# Sheet1.net
KiCad netlist of a schematic drawn in Altium Designer
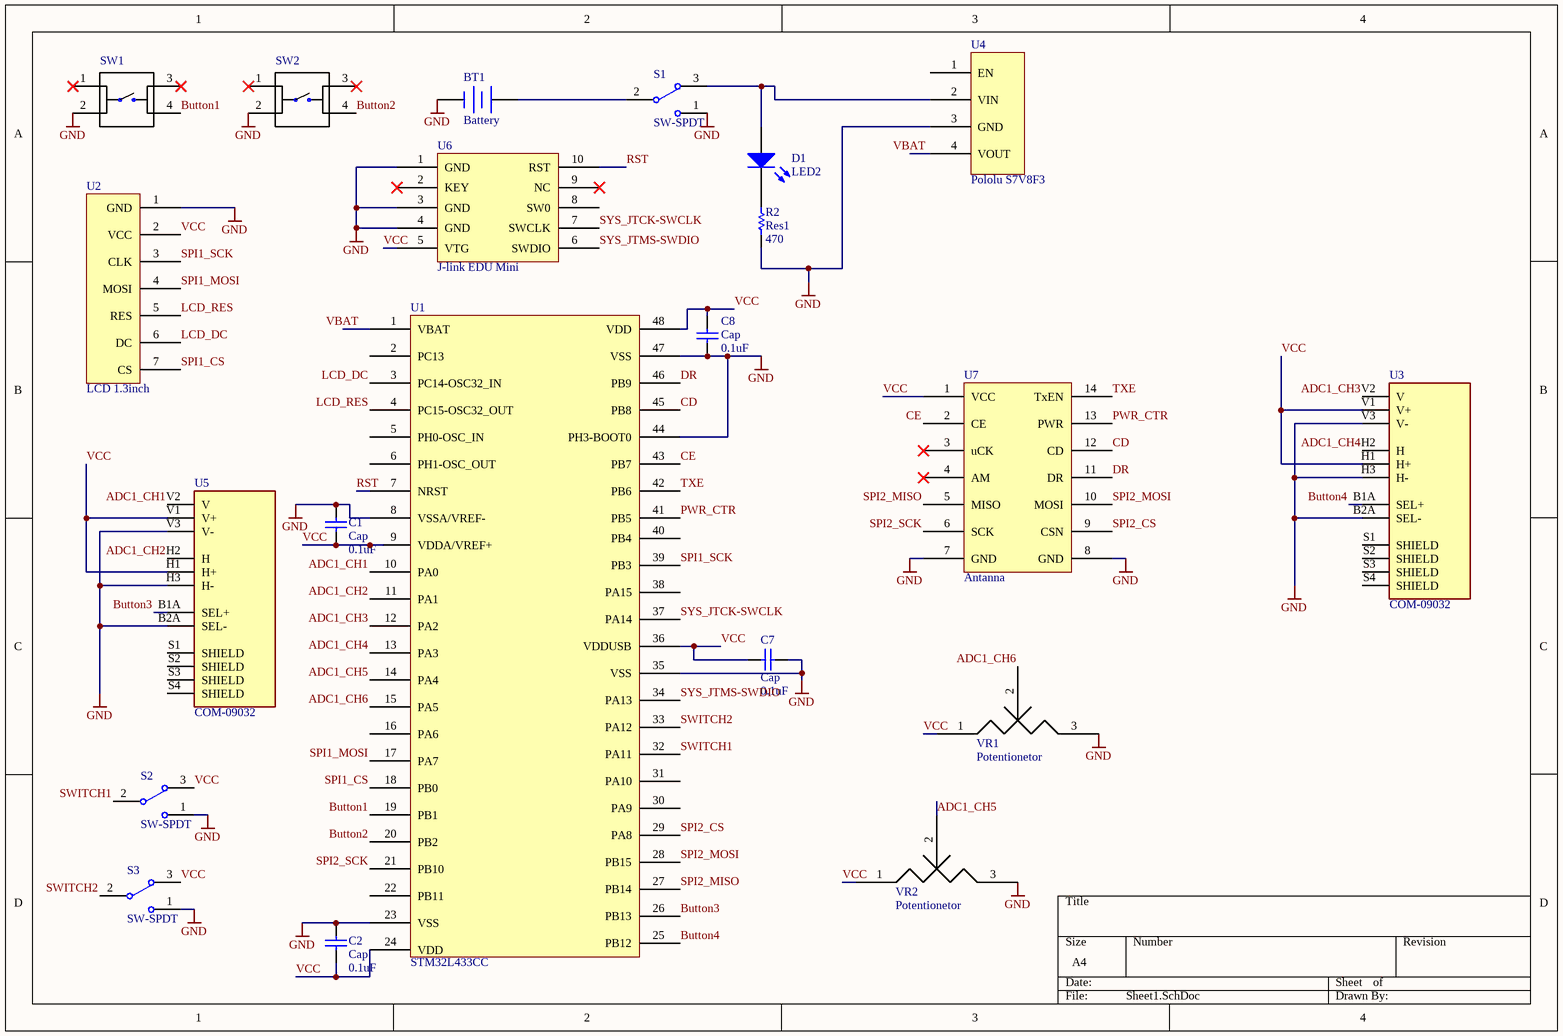
[diagram p0: Sheet1.SchDoc]

(export (version "E")
  (design (tool "Eeschema 10.0.6"))
  (components
    (comp (ref "BT1")
      (value "Battery")
      (footprint "BAT-2")
      (description "Multicell Battery")
      (fields (field (name "PUBLISHER") "Altium Limited"))
      (libsource (lib "Miscellaneous Devices") (part "Battery"))
    )
    (comp (ref "C1")
      (value "Cap")
      (footprint "RESC0603")
      (description "Capacitor")
      (fields (field (name "ALTIUM_VALUE") "0.1uF") (field (name "PUBLISHER") "Altium Limited"))
      (libsource (lib "Miscellaneous Devices") (part "Cap"))
    )
    (comp (ref "C2")
      (value "Cap")
      (footprint "RESC0603")
      (description "Capacitor")
      (fields (field (name "ALTIUM_VALUE") "0.1uF") (field (name "PUBLISHER") "Altium Limited"))
      (libsource (lib "Miscellaneous Devices") (part "Cap"))
    )
    (comp (ref "C7")
      (value "Cap")
      (footprint "RESC0603")
      (description "Capacitor")
      (fields (field (name "ALTIUM_VALUE") "0.1uF") (field (name "PUBLISHER") "Altium Limited"))
      (libsource (lib "Miscellaneous Devices") (part "Cap"))
    )
    (comp (ref "C8")
      (value "Cap")
      (footprint "RESC0603")
      (description "Capacitor")
      (fields (field (name "ALTIUM_VALUE") "0.1uF") (field (name "PUBLISHER") "Altium Limited"))
      (libsource (lib "Miscellaneous Devices") (part "Cap"))
    )
    (comp (ref "D1")
      (value "LED2")
      (footprint "LED1")
      (description "Typical RED, GREEN, YELLOW, AMBER GaAs LED")
      (fields (field (name "PUBLISHER") "Altium Limited"))
      (libsource (lib "Miscellaneous Devices") (part "LED2"))
    )
    (comp (ref "R2")
      (value "Res1")
      (footprint "RESC0603")
      (description "Resistor")
      (fields (field (name "ALTIUM_VALUE") "470") (field (name "PUBLISHER") "Altium Limited"))
      (libsource (lib "Miscellaneous Devices") (part "Res1"))
    )
    (comp (ref "S1")
      (value "SW-SPDT")
      (footprint "Toggle switch")
      (description "SPDT Subminiature Toggle Switch, Right Angle Mounting, Vertical Actuation")
      (fields (field (name "PUBLISHER") "Altium Limited"))
      (libsource (lib "Miscellaneous Devices") (part "SW-SPDT"))
    )
    (comp (ref "S2")
      (value "SW-SPDT")
      (footprint "Toggle switch")
      (description "SPDT Subminiature Toggle Switch, Right Angle Mounting, Vertical Actuation")
      (fields (field (name "PUBLISHER") "Altium Limited"))
      (libsource (lib "Miscellaneous Devices") (part "SW-SPDT"))
    )
    (comp (ref "S3")
      (value "SW-SPDT")
      (footprint "Toggle switch")
      (description "SPDT Subminiature Toggle Switch, Right Angle Mounting, Vertical Actuation")
      (fields (field (name "PUBLISHER") "Altium Limited"))
      (libsource (lib "Miscellaneous Devices") (part "SW-SPDT"))
    )
    (comp (ref "SW1")
      (value "1825910-6")
      (footprint "PUSHBUTTON SWITCH - duplicate")
      (description "6MM TACT SWITCH, HIGH TEMP")
      (fields (field (name "DIGI-KEY_PART_NUMBER") "450-1650-ND") (field (name "MF") "TE Connectivity"))
      (libsource (lib "Schlib1") (part "1825910-6"))
    )
    (comp (ref "SW2")
      (value "1825910-6")
      (footprint "PUSHBUTTON SWITCH - duplicate")
      (description "6MM TACT SWITCH, HIGH TEMP")
      (fields (field (name "DIGI-KEY_PART_NUMBER") "450-1650-ND") (field (name "MF") "TE Connectivity"))
      (libsource (lib "Schlib1") (part "1825910-6"))
    )
    (comp (ref "U1")
      (value "STM32L433CC")
      (footprint "LQFP48")
      (libsource (lib "Schlib1") (part "STM32L433CC"))
    )
    (comp (ref "U2")
      (value "LCD 1.3inch")
      (footprint "LCD")
      (libsource (lib "Schlib_Controller") (part "LCD 1.3inch"))
    )
    (comp (ref "U3")
      (value "COM-09032")
      (footprint "XDCR_COM-09032")
      (description "Joystick, 2 - Axis Analog _Resistive_ Output")
      (fields (field (name "MF") "SparkFun Electronics"))
      (libsource (lib "Schlib_Controller") (part "COM-09032"))
    )
    (comp (ref "U4")
      (value "Pololu S7V8F3")
      (footprint "Pololu S7V8F3")
      (libsource (lib "Schlib1") (part "Pololu S7V8F3"))
    )
    (comp (ref "U5")
      (value "COM-09032")
      (footprint "XDCR_COM-09032")
      (description "Joystick, 2 - Axis Analog _Resistive_ Output")
      (fields (field (name "MF") "SparkFun Electronics"))
      (libsource (lib "Schlib_Controller") (part "COM-09032"))
    )
    (comp (ref "U6")
      (value "J-link EDU Mini")
      (footprint "10 pin vertical")
      (libsource (lib "Schlib1") (part "J-link EDU Mini"))
    )
    (comp (ref "U7")
      (value "Antanna")
      (footprint "Antanna")
      (libsource (lib "Schlib_Controller") (part "Antanna"))
    )
    (comp (ref "VR1")
      (value "Potentionetor")
      (footprint "potentiometer")
      (libsource (lib "Schlib_Controller") (part "Potentionetor"))
    )
    (comp (ref "VR2")
      (value "Potentionetor")
      (footprint "potentiometer")
      (libsource (lib "Schlib_Controller") (part "Potentionetor"))
    )
  )
  (nets
    (net (code "1") (name "/ADC1_CH1") (class "Default")
      (node (ref "U1") (pin "10") (pinfunction "PA0_10") (pintype "passive"))
      (node (ref "U5") (pin "V2") (pinfunction "V_V2") (pintype "passive"))
    )
    (net (code "2") (name "/ADC1_CH2") (class "Default")
      (node (ref "U1") (pin "11") (pinfunction "PA1_11") (pintype "passive"))
      (node (ref "U5") (pin "H2") (pinfunction "H_H2") (pintype "passive"))
    )
    (net (code "3") (name "/ADC1_CH3") (class "Default")
      (node (ref "U1") (pin "12") (pinfunction "PA2_12") (pintype "passive"))
      (node (ref "U3") (pin "V2") (pinfunction "V_V2") (pintype "passive"))
    )
    (net (code "4") (name "/ADC1_CH4") (class "Default")
      (node (ref "U1") (pin "13") (pinfunction "PA3_13") (pintype "passive"))
      (node (ref "U3") (pin "H2") (pinfunction "H_H2") (pintype "passive"))
    )
    (net (code "5") (name "/ADC1_CH5") (class "Default")
      (node (ref "U1") (pin "14") (pinfunction "PA4_14") (pintype "passive"))
      (node (ref "VR2") (pin "2") (pintype "passive"))
    )
    (net (code "6") (name "/ADC1_CH6") (class "Default")
      (node (ref "U1") (pin "15") (pinfunction "PA5_15") (pintype "passive"))
      (node (ref "VR1") (pin "2") (pintype "passive"))
    )
    (net (code "7") (name "/Button1") (class "Default")
      (node (ref "SW1") (pin "4") (pinfunction "4_4") (pintype "passive"))
      (node (ref "U1") (pin "19") (pinfunction "PB1_19") (pintype "passive"))
    )
    (net (code "8") (name "/Button2") (class "Default")
      (node (ref "SW2") (pin "4") (pinfunction "4_4") (pintype "passive"))
      (node (ref "U1") (pin "20") (pinfunction "PB2_20") (pintype "passive"))
    )
    (net (code "9") (name "/Button3") (class "Default")
      (node (ref "U1") (pin "26") (pinfunction "PB13_26") (pintype "passive"))
      (node (ref "U5") (pin "B1A") (pinfunction "SEL+_B1A") (pintype "passive"))
    )
    (net (code "10") (name "/Button4") (class "Default")
      (node (ref "U1") (pin "25") (pinfunction "PB12_25") (pintype "passive"))
      (node (ref "U3") (pin "B1A") (pinfunction "SEL+_B1A") (pintype "passive"))
    )
    (net (code "11") (name "/CD") (class "Default")
      (node (ref "U1") (pin "45") (pinfunction "PB8_45") (pintype "passive"))
      (node (ref "U7") (pin "12") (pinfunction "CD_12") (pintype "passive"))
    )
    (net (code "12") (name "/CE") (class "Default")
      (node (ref "U1") (pin "43") (pinfunction "PB7_43") (pintype "passive"))
      (node (ref "U7") (pin "2") (pinfunction "CE_2") (pintype "passive"))
    )
    (net (code "13") (name "/DR") (class "Default")
      (node (ref "U1") (pin "46") (pinfunction "PB9_46") (pintype "passive"))
      (node (ref "U7") (pin "11") (pinfunction "DR_11") (pintype "passive"))
    )
    (net (code "14") (name "/LCD_DC") (class "Default")
      (node (ref "U1") (pin "3") (pinfunction "PC14-OSC32_IN_3") (pintype "passive"))
      (node (ref "U2") (pin "6") (pinfunction "DC_6") (pintype "passive"))
    )
    (net (code "15") (name "/LCD_RES") (class "Default")
      (node (ref "U1") (pin "4") (pinfunction "PC15-OSC32_OUT_4") (pintype "passive"))
      (node (ref "U2") (pin "5") (pinfunction "RES_5") (pintype "passive"))
    )
    (net (code "16") (name "/PWR_CTR") (class "Default")
      (node (ref "U1") (pin "41") (pinfunction "PB5_41") (pintype "passive"))
      (node (ref "U7") (pin "13") (pinfunction "PWR_13") (pintype "passive"))
    )
    (net (code "17") (name "/RST") (class "Default")
      (node (ref "U1") (pin "7") (pinfunction "NRST_7") (pintype "passive"))
      (node (ref "U6") (pin "10") (pinfunction "RST_10") (pintype "passive"))
    )
    (net (code "18") (name "/SPI1_CS") (class "Default")
      (node (ref "U1") (pin "18") (pinfunction "PB0_18") (pintype "passive"))
      (node (ref "U2") (pin "7") (pinfunction "CS_7") (pintype "passive"))
    )
    (net (code "19") (name "/SPI1_MOSI") (class "Default")
      (node (ref "U1") (pin "17") (pinfunction "PA7_17") (pintype "passive"))
      (node (ref "U2") (pin "4") (pinfunction "MOSI_4") (pintype "passive"))
    )
    (net (code "20") (name "/SPI1_SCK") (class "Default")
      (node (ref "U1") (pin "39") (pinfunction "PB3_39") (pintype "passive"))
      (node (ref "U2") (pin "3") (pinfunction "CLK_3") (pintype "passive"))
    )
    (net (code "21") (name "/SPI2_CS") (class "Default")
      (node (ref "U1") (pin "29") (pinfunction "PA8_29") (pintype "passive"))
      (node (ref "U7") (pin "9") (pinfunction "CSN_9") (pintype "passive"))
    )
    (net (code "22") (name "/SPI2_MISO") (class "Default")
      (node (ref "U1") (pin "27") (pinfunction "PB14_27") (pintype "passive"))
      (node (ref "U7") (pin "5") (pinfunction "MISO_5") (pintype "passive"))
    )
    (net (code "23") (name "/SPI2_MOSI") (class "Default")
      (node (ref "U1") (pin "28") (pinfunction "PB15_28") (pintype "passive"))
      (node (ref "U7") (pin "10") (pinfunction "MOSI_10") (pintype "passive"))
    )
    (net (code "24") (name "/SPI2_SCK") (class "Default")
      (node (ref "U1") (pin "21") (pinfunction "PB10_21") (pintype "passive"))
      (node (ref "U7") (pin "6") (pinfunction "SCK_6") (pintype "passive"))
    )
    (net (code "25") (name "/SWITCH1") (class "Default")
      (node (ref "S2") (pin "2") (pinfunction "2_2") (pintype "passive"))
      (node (ref "U1") (pin "32") (pinfunction "PA11_32") (pintype "passive"))
    )
    (net (code "26") (name "/SWITCH2") (class "Default")
      (node (ref "S3") (pin "2") (pinfunction "2_2") (pintype "passive"))
      (node (ref "U1") (pin "33") (pinfunction "PA12_33") (pintype "passive"))
    )
    (net (code "27") (name "/SYS_JTCK-SWCLK") (class "Default")
      (node (ref "U1") (pin "37") (pinfunction "PA14_37") (pintype "passive"))
      (node (ref "U6") (pin "7") (pinfunction "SWCLK_7") (pintype "passive"))
    )
    (net (code "28") (name "/SYS_JTMS-SWDIO") (class "Default")
      (node (ref "U1") (pin "34") (pinfunction "PA13_34") (pintype "passive"))
      (node (ref "U6") (pin "6") (pinfunction "SWDIO_6") (pintype "passive"))
    )
    (net (code "29") (name "/TXE") (class "Default")
      (node (ref "U1") (pin "42") (pinfunction "PB6_42") (pintype "passive"))
      (node (ref "U7") (pin "14") (pinfunction "TxEN_14") (pintype "passive"))
    )
    (net (code "30") (name "/VBAT") (class "Default")
      (node (ref "U1") (pin "1") (pinfunction "VBAT_1") (pintype "passive"))
      (node (ref "U4") (pin "4") (pinfunction "VOUT_4") (pintype "passive"))
    )
    (net (code "31") (name "/VCC") (class "Default")
      (node (ref "C1") (pin "1") (pinfunction "1_1") (pintype "passive"))
      (node (ref "C2") (pin "1") (pinfunction "1_1") (pintype "passive"))
      (node (ref "C7") (pin "2") (pinfunction "2_2") (pintype "passive"))
      (node (ref "C8") (pin "2") (pinfunction "2_2") (pintype "passive"))
      (node (ref "S2") (pin "3") (pinfunction "3_3") (pintype "passive"))
      (node (ref "S3") (pin "3") (pinfunction "3_3") (pintype "passive"))
      (node (ref "U1") (pin "24") (pinfunction "VDD_24") (pintype "passive"))
      (node (ref "U1") (pin "36") (pinfunction "VDDUSB_36") (pintype "passive"))
      (node (ref "U1") (pin "48") (pinfunction "VDD_48") (pintype "passive"))
      (node (ref "U1") (pin "9") (pinfunction "VDDA/VREF+_9") (pintype "passive"))
      (node (ref "U2") (pin "2") (pinfunction "VCC_2") (pintype "passive"))
      (node (ref "U3") (pin "H1") (pinfunction "H+_H1") (pintype "passive"))
      (node (ref "U3") (pin "V1") (pinfunction "V+_V1") (pintype "passive"))
      (node (ref "U5") (pin "H1") (pinfunction "H+_H1") (pintype "passive"))
      (node (ref "U5") (pin "V1") (pinfunction "V+_V1") (pintype "passive"))
      (node (ref "U6") (pin "5") (pinfunction "VTG_5") (pintype "passive"))
      (node (ref "U7") (pin "1") (pinfunction "VCC_1") (pintype "passive"))
      (node (ref "VR1") (pin "1") (pintype "passive"))
      (node (ref "VR2") (pin "1") (pintype "passive"))
    )
    (net (code "32") (name "GND") (class "Default")
      (node (ref "BT1") (pin "2") (pinfunction "-_2") (pintype "passive"))
      (node (ref "C1") (pin "2") (pinfunction "2_2") (pintype "passive"))
      (node (ref "C2") (pin "2") (pinfunction "2_2") (pintype "passive"))
      (node (ref "C7") (pin "1") (pinfunction "1_1") (pintype "passive"))
      (node (ref "C8") (pin "1") (pinfunction "1_1") (pintype "passive"))
      (node (ref "R2") (pin "1") (pinfunction "1_1") (pintype "passive"))
      (node (ref "S1") (pin "1") (pinfunction "1_1") (pintype "passive"))
      (node (ref "S2") (pin "1") (pinfunction "1_1") (pintype "passive"))
      (node (ref "S3") (pin "1") (pinfunction "1_1") (pintype "passive"))
      (node (ref "SW1") (pin "2") (pinfunction "2_2") (pintype "passive"))
      (node (ref "SW2") (pin "2") (pinfunction "2_2") (pintype "passive"))
      (node (ref "U1") (pin "23") (pinfunction "VSS_23") (pintype "passive"))
      (node (ref "U1") (pin "35") (pinfunction "VSS_35") (pintype "passive"))
      (node (ref "U1") (pin "44") (pinfunction "PH3-BOOT0_44") (pintype "passive"))
      (node (ref "U1") (pin "47") (pinfunction "VSS_47") (pintype "passive"))
      (node (ref "U1") (pin "8") (pinfunction "VSSA/VREF-_8") (pintype "passive"))
      (node (ref "U2") (pin "1") (pinfunction "GND_1") (pintype "passive"))
      (node (ref "U3") (pin "B2A") (pinfunction "SEL-_B2A") (pintype "passive"))
      (node (ref "U3") (pin "H3") (pinfunction "H-_H3") (pintype "passive"))
      (node (ref "U3") (pin "V3") (pinfunction "V-_V3") (pintype "passive"))
      (node (ref "U4") (pin "3") (pinfunction "GND_3") (pintype "passive"))
      (node (ref "U5") (pin "B2A") (pinfunction "SEL-_B2A") (pintype "passive"))
      (node (ref "U5") (pin "H3") (pinfunction "H-_H3") (pintype "passive"))
      (node (ref "U5") (pin "V3") (pinfunction "V-_V3") (pintype "passive"))
      (node (ref "U6") (pin "1") (pinfunction "GND_1") (pintype "passive"))
      (node (ref "U6") (pin "3") (pinfunction "GND_3") (pintype "passive"))
      (node (ref "U6") (pin "4") (pinfunction "GND_4") (pintype "passive"))
      (node (ref "U7") (pin "7") (pinfunction "GND_7") (pintype "passive"))
      (node (ref "U7") (pin "8") (pinfunction "GND_8") (pintype "passive"))
      (node (ref "VR1") (pin "3") (pintype "passive"))
      (node (ref "VR2") (pin "3") (pintype "passive"))
    )
    (net (code "33") (name "Net-(BT1-+)") (class "Default")
      (node (ref "BT1") (pin "1") (pinfunction "+_1") (pintype "passive"))
      (node (ref "S1") (pin "2") (pinfunction "2_2") (pintype "passive"))
    )
    (net (code "34") (name "Net-(D1-A)") (class "Default")
      (node (ref "D1") (pin "1") (pinfunction "A_1") (pintype "passive"))
      (node (ref "S1") (pin "3") (pinfunction "3_3") (pintype "passive"))
      (node (ref "U4") (pin "2") (pinfunction "VIN_2") (pintype "passive"))
    )
    (net (code "35") (name "Net-(D1-K)") (class "Default")
      (node (ref "D1") (pin "2") (pinfunction "K_2") (pintype "passive"))
      (node (ref "R2") (pin "2") (pinfunction "2_2") (pintype "passive"))
    )
    (net (code "36") (name "unconnected-(SW1-Pad1)") (class "Default")
      (node (ref "SW1") (pin "1") (pinfunction "1_1") (pintype "passive+no_connect"))
    )
    (net (code "37") (name "unconnected-(SW1-Pad3)") (class "Default")
      (node (ref "SW1") (pin "3") (pinfunction "3_3") (pintype "passive+no_connect"))
    )
    (net (code "38") (name "unconnected-(SW2-Pad1)") (class "Default")
      (node (ref "SW2") (pin "1") (pinfunction "1_1") (pintype "passive+no_connect"))
    )
    (net (code "39") (name "unconnected-(SW2-Pad3)") (class "Default")
      (node (ref "SW2") (pin "3") (pinfunction "3_3") (pintype "passive+no_connect"))
    )
    (net (code "40") (name "unconnected-(U1-PA6-Pad16)") (class "Default")
      (node (ref "U1") (pin "16") (pinfunction "PA6_16") (pintype "passive"))
    )
    (net (code "41") (name "unconnected-(U1-PA9-Pad30)") (class "Default")
      (node (ref "U1") (pin "30") (pinfunction "PA9_30") (pintype "passive"))
    )
    (net (code "42") (name "unconnected-(U1-PA10-Pad31)") (class "Default")
      (node (ref "U1") (pin "31") (pinfunction "PA10_31") (pintype "passive"))
    )
    (net (code "43") (name "unconnected-(U1-PA15-Pad38)") (class "Default")
      (node (ref "U1") (pin "38") (pinfunction "PA15_38") (pintype "passive"))
    )
    (net (code "44") (name "unconnected-(U1-PB4-Pad40)") (class "Default")
      (node (ref "U1") (pin "40") (pinfunction "PB4_40") (pintype "passive"))
    )
    (net (code "45") (name "unconnected-(U1-PB11-Pad22)") (class "Default")
      (node (ref "U1") (pin "22") (pinfunction "PB11_22") (pintype "passive"))
    )
    (net (code "46") (name "unconnected-(U1-PC13-Pad2)") (class "Default")
      (node (ref "U1") (pin "2") (pinfunction "PC13_2") (pintype "passive"))
    )
    (net (code "47") (name "unconnected-(U1-PH0-OSC_IN-Pad5)") (class "Default")
      (node (ref "U1") (pin "5") (pinfunction "PH0-OSC_IN_5") (pintype "passive"))
    )
    (net (code "48") (name "unconnected-(U1-PH1-OSC_OUT-Pad6)") (class "Default")
      (node (ref "U1") (pin "6") (pinfunction "PH1-OSC_OUT_6") (pintype "passive"))
    )
    (net (code "49") (name "unconnected-(U3-SHIELD-PadS1)") (class "Default")
      (node (ref "U3") (pin "S1") (pinfunction "SHIELD_S1") (pintype "passive"))
    )
    (net (code "50") (name "unconnected-(U3-SHIELD-PadS2)") (class "Default")
      (node (ref "U3") (pin "S2") (pinfunction "SHIELD_S2") (pintype "passive"))
    )
    (net (code "51") (name "unconnected-(U3-SHIELD-PadS3)") (class "Default")
      (node (ref "U3") (pin "S3") (pinfunction "SHIELD_S3") (pintype "passive"))
    )
    (net (code "52") (name "unconnected-(U3-SHIELD-PadS4)") (class "Default")
      (node (ref "U3") (pin "S4") (pinfunction "SHIELD_S4") (pintype "passive"))
    )
    (net (code "53") (name "unconnected-(U4-EN-Pad1)") (class "Default")
      (node (ref "U4") (pin "1") (pinfunction "EN_1") (pintype "passive"))
    )
    (net (code "54") (name "unconnected-(U5-SHIELD-PadS1)") (class "Default")
      (node (ref "U5") (pin "S1") (pinfunction "SHIELD_S1") (pintype "passive"))
    )
    (net (code "55") (name "unconnected-(U5-SHIELD-PadS2)") (class "Default")
      (node (ref "U5") (pin "S2") (pinfunction "SHIELD_S2") (pintype "passive"))
    )
    (net (code "56") (name "unconnected-(U5-SHIELD-PadS3)") (class "Default")
      (node (ref "U5") (pin "S3") (pinfunction "SHIELD_S3") (pintype "passive"))
    )
    (net (code "57") (name "unconnected-(U5-SHIELD-PadS4)") (class "Default")
      (node (ref "U5") (pin "S4") (pinfunction "SHIELD_S4") (pintype "passive"))
    )
    (net (code "58") (name "unconnected-(U6-KEY-Pad2)") (class "Default")
      (node (ref "U6") (pin "2") (pinfunction "KEY_2") (pintype "passive+no_connect"))
    )
    (net (code "59") (name "unconnected-(U6-NC-Pad9)") (class "Default")
      (node (ref "U6") (pin "9") (pinfunction "NC_9") (pintype "passive+no_connect"))
    )
    (net (code "60") (name "unconnected-(U6-SW0-Pad8)") (class "Default")
      (node (ref "U6") (pin "8") (pinfunction "SW0_8") (pintype "passive"))
    )
    (net (code "61") (name "unconnected-(U7-AM-Pad4)") (class "Default")
      (node (ref "U7") (pin "4") (pinfunction "AM_4") (pintype "passive+no_connect"))
    )
    (net (code "62") (name "unconnected-(U7-uCK-Pad3)") (class "Default")
      (node (ref "U7") (pin "3") (pinfunction "uCK_3") (pintype "passive+no_connect"))
    )
  )
)
